# TEMPLATE_Circuit.net
KiCad netlist of a schematic drawn in Altium Designer
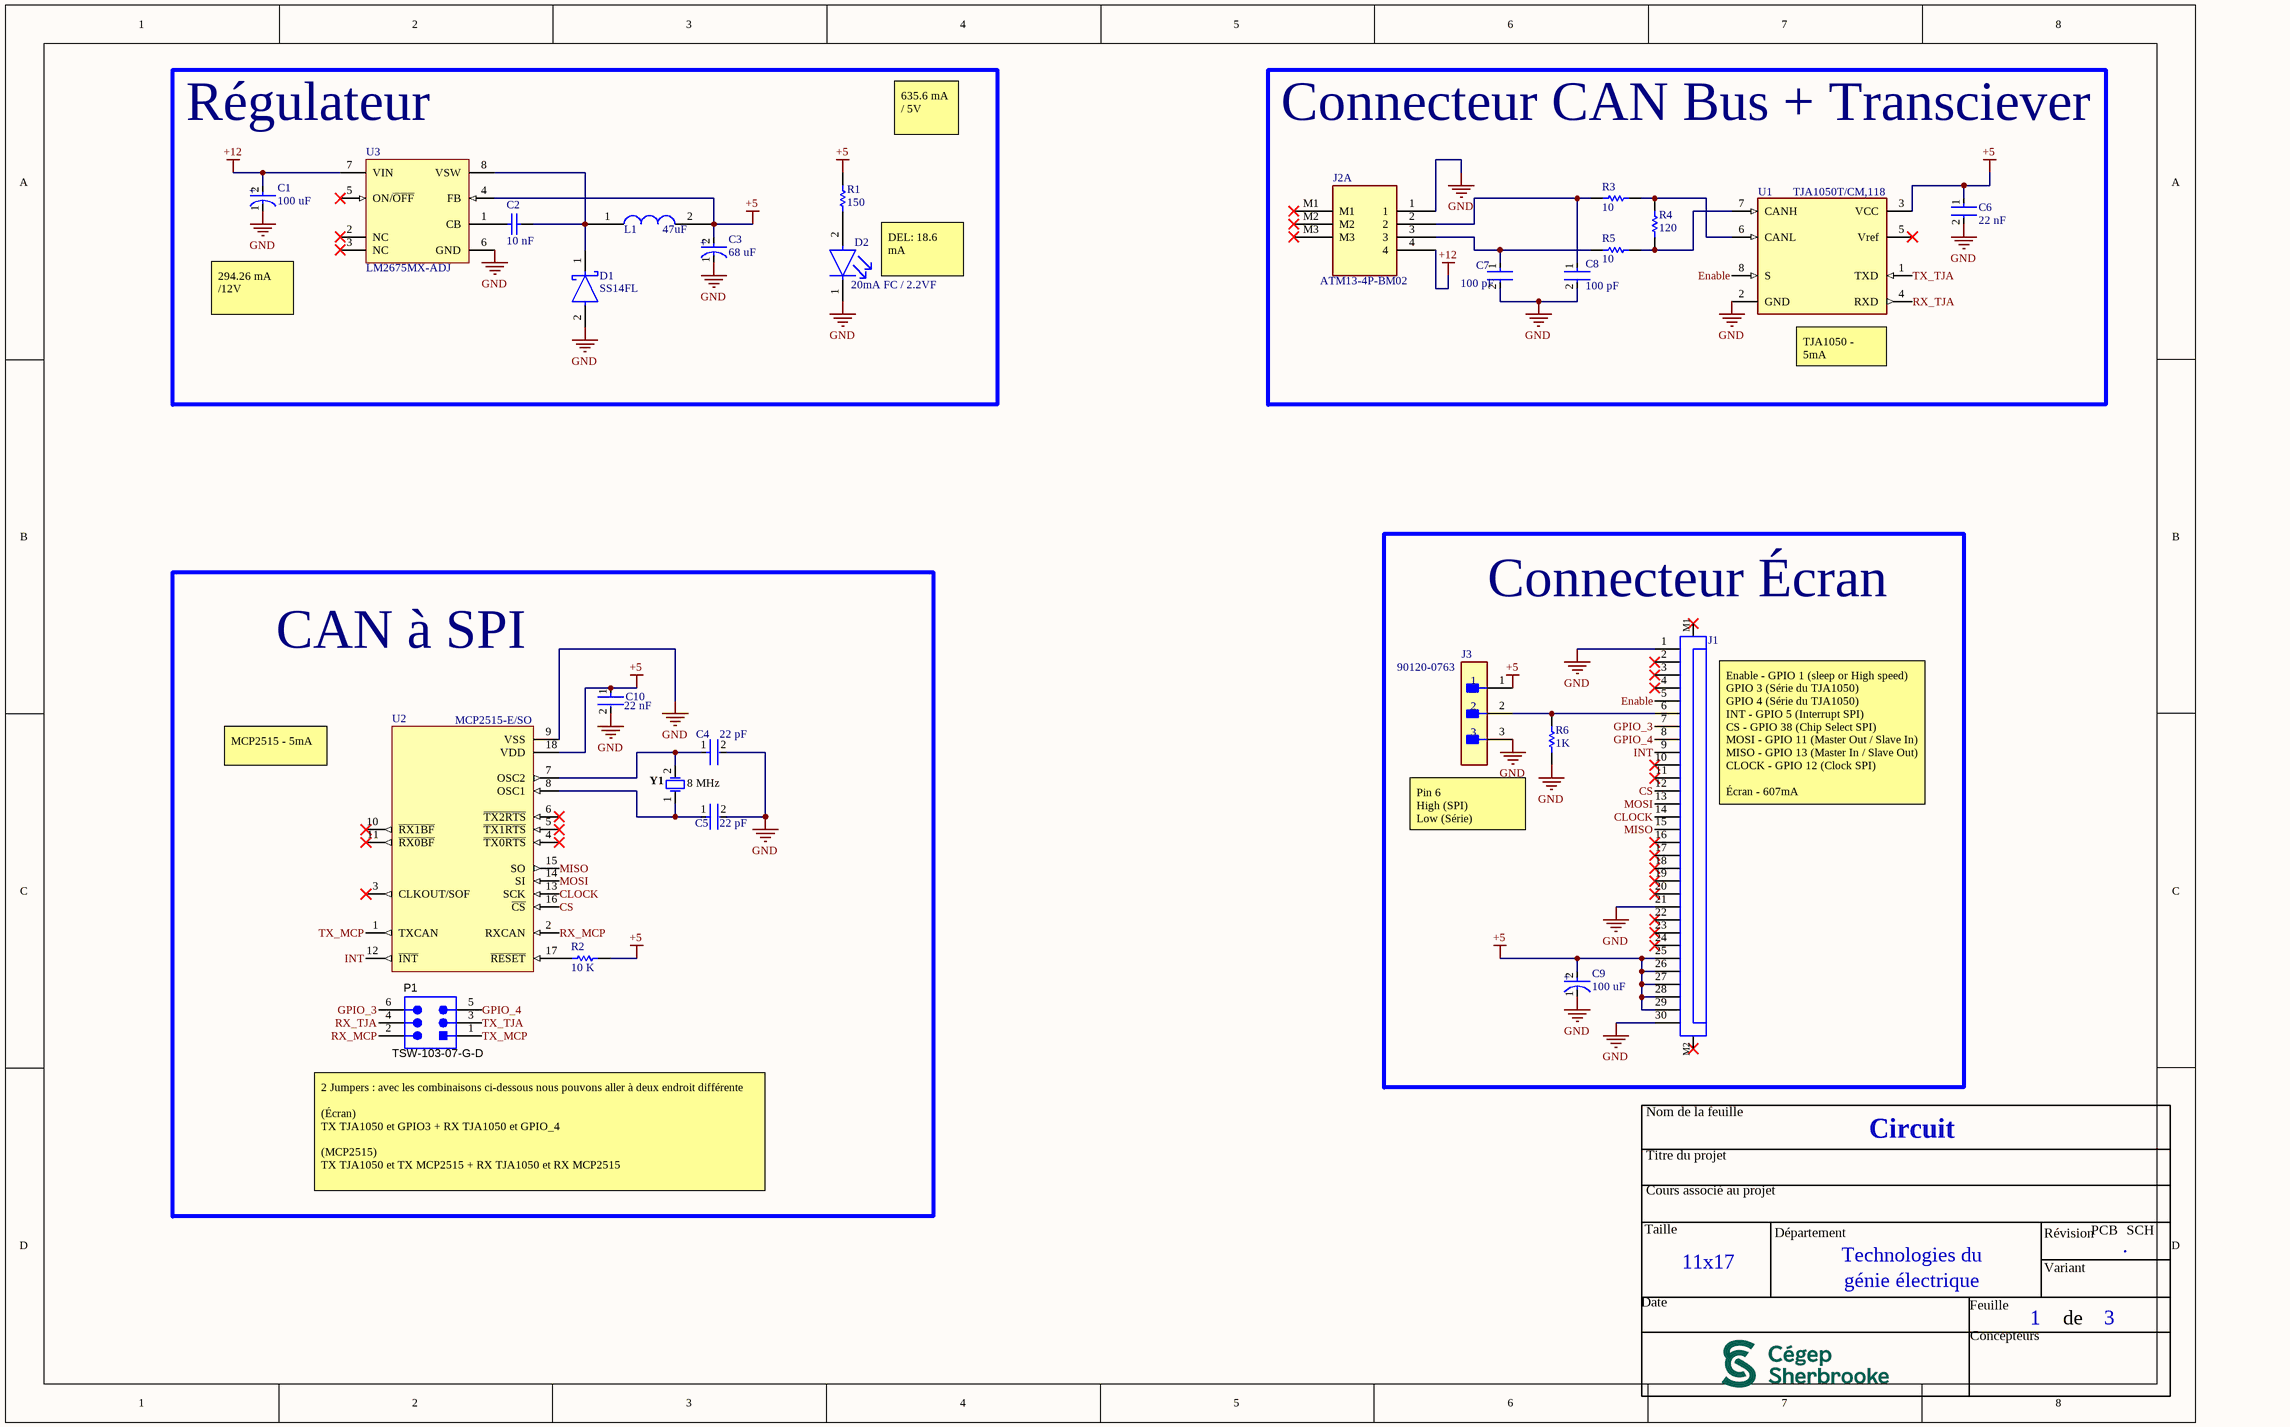
[diagram p0: TEMPLATE_Circuit.SchDoc]

(export (version "E")
  (design (tool "Eeschema 10.0.6"))
  (components
    (comp (ref "C1")
      (value "100 uF")
      (footprint "FP-FKF-MFG")
      (description "CAP ALUM 100UF 20% 50V SMD")
      (fields (field (name "VOLTAGE") "50V") (field (name "TOLERANCE") "20%"))
      (libsource (lib "Altium Content Vault") (part "a00bbbee19879c290e62620ae7e47b1"))
    )
    (comp (ref "C2")
      (value "10 nF")
      (footprint "CAPC1608X90X35ML10T15")
      (description "Chip Capacitor, 10 nF, +/- 10%, 50 V, -55 to 125 degC, 0603 (1608 Metric), RoHS, Tape and Reel")
      (fields (field (name "VOLTAGE") "50V") (field (name "TOLERANCE") "10%"))
      (libsource (lib "Altium Content Vault") (part "CAP-NP-2"))
    )
    (comp (ref "C3")
      (value "68 uF")
      (footprint "FP-OS-CON-SMT-F12-MFG")
      (description "Conductive Polymer Aluminum Solid Capacitors (OS-CON) 68uF ±20% 50V RADIAL SMT 10x12.6mm")
      (fields (field (name "TOLERANCE") "20%") (field (name "VOLTAGE") "50V"))
      (libsource (lib "Altium Content Vault") (part "a7907c86e72a156c28511143de7831b"))
    )
    (comp (ref "C4")
      (value "22 pF")
      (footprint "FP-C0805C-DN-MFG")
      (description "Capacitor; Ceramic; Cap; 22.0pF; Tol 5%; SMT; Vol-Rtg 50V; C0G; Tape and Reel")
      (fields
        (field (name "OCTOPART") "https://octopart.com/c0805c220j5gactu-kemet-145470")
        (field (name "MANUFACTURER") "KEMET")
      )
      (libsource (lib "Altium Content Vault") (part "b4654b650e69147ec39a6b967a45e02"))
    )
    (comp (ref "C5")
      (value "22 pF")
      (footprint "FP-C0805C-DN-MFG")
      (description "Capacitor; Ceramic; Cap; 22.0pF; Tol 5%; SMT; Vol-Rtg 50V; C0G; Tape and Reel")
      (fields
        (field (name "OCTOPART") "https://octopart.com/c0805c220j5gactu-kemet-145470")
        (field (name "MANUFACTURER") "KEMET")
      )
      (libsource (lib "Altium Content Vault") (part "b4654b650e69147ec39a6b967a45e02"))
    )
    (comp (ref "C6")
      (value "22 nF")
      (footprint "FP-C0805C-DN-MFG")
      (description "CAP CER 0.022UF 50V X7R 0805")
      (fields
        (field (name "MANUFACTURER") "KEMET")
        (field (name "MANUFACTURER PART NUMBER") "C0805C223K5RACTU")
      )
      (libsource (lib "Altium Content Vault") (part "b4654b650e69147ec39a6b967a45e02"))
    )
    (comp (ref "C7")
      (value "100 pF")
      (footprint "FP-CC0805-0_1-0_7-IPC_A")
      (description "CAP CER 100PF 50V C0G/NPO 0805")
      (fields (field (name "VOLTAGE") "50V") (field (name "TOLERANCE") "5%"))
      (libsource (lib "Altium Content Vault") (part "02cd4be3c70576c341d710602a673aa"))
    )
    (comp (ref "C8")
      (value "100 pF")
      (footprint "FP-CC0805-0_1-0_7-IPC_A")
      (description "CAP CER 100PF 50V C0G/NPO 0805")
      (fields (field (name "VOLTAGE") "50V") (field (name "TOLERANCE") "5%"))
      (libsource (lib "Altium Content Vault") (part "02cd4be3c70576c341d710602a673aa"))
    )
    (comp (ref "C9")
      (value "100 uF")
      (footprint "FP-FKF-MFG")
      (description "CAP ALUM 100UF 20% 50V SMD")
      (fields (field (name "VOLTAGE") "50V") (field (name "TOLERANCE") "20%"))
      (libsource (lib "Altium Content Vault") (part "a00bbbee19879c290e62620ae7e47b1"))
    )
    (comp (ref "C10")
      (value "22 nF")
      (footprint "FP-C0805C-DN-MFG")
      (description "CAP CER 0.022UF 50V X7R 0805")
      (fields
        (field (name "MANUFACTURER") "KEMET")
        (field (name "MANUFACTURER PART NUMBER") "C0805C223K5RACTU")
      )
      (libsource (lib "Altium Content Vault") (part "b4654b650e69147ec39a6b967a45e02"))
    )
    (comp (ref "D1")
      (value "SS14FL")
      (footprint "FP-425AD-MFG")
      (description "DIODE SCHOTTKY 40V 1A SOD123F")
      (fields
        (field (name "MANUFACTURER") "ON Semiconductor")
        (field (name "OCTOPART") "https://octopart.com/ss14fl-on+semiconductor-84331601")
      )
      (libsource (lib "Altium Content Vault") (part "c1678fac7984e62e0809fbf79c06691"))
    )
    (comp (ref "D2")
      (value "20mA FC / 2.2VF")
      (footprint "FP-SML-210-MFG")
      (description "LED GREEN CLEAR 0805 SMD")
      (fields (field (name "MANUFACTURER PART NUMBER") "SML-210MTT86") (field (name "MANUFACTURER") "ROHM"))
      (libsource (lib "Altium Content Vault") (part "8706943c75ba83719d021d2fdc84c58"))
    )
    (comp (ref "J1")
      (value "68613014422")
      (footprint "68613014422")
      (libsource (lib "Altium Content Vault") (part "FPC - 30P - 2MP"))
    )
    (comp (ref "J2")
      (value "ATM13-4P-BM02")
      (footprint "ATM134PBM02")
      (libsource (lib "PCB_MCP_Final") (part "ATM13-4P-BM02"))
    )
    (comp (ref "J3")
      (value "90120-0763")
      (footprint "FP-90120-0763-MFG")
      (description "CONN HEADER VERT 3POS 2.54MM")
      (fields
        (field (name "MANUFACTURER") "Molex")
        (field (name "OCTOPART") "https://octopart.com/90120-0763-molex-655433")
      )
      (libsource (lib "Altium Content Vault") (part "0d3f023dd272f625e17a2be33dea85f"))
    )
    (comp (ref "L1")
      (value "47uF")
      (footprint "NPI31W470MTRF")
      (libsource (lib "NPI31W470MTRF") (part "TEMPLATE_Circuit"))
    )
    (comp (ref "P1")
      (value "TSW-103-07-G-D")
      (footprint "SMTC-TSW-103-07-G-D_V")
      (fields (field (name "MANUFACTURER") "Samtec-Inc."))
      (libsource (lib "Altium Content Vault") (part "CN-2P-M-R6"))
    )
    (comp (ref "R1")
      (value "150")
      (footprint "RESC2013X60X40NL20T25")
      (fields (field (name "MANUFACTURER") "Panasonic") (field (name "PART NUMBER") "ERA6AEB151V"))
      (libsource (lib "Altium Content Vault") (part "RES"))
    )
    (comp (ref "R2")
      (value "10 K")
      (footprint "RESC2013X60X35NL10T20")
      (description "Chip Resistor, 10 KOhm, +/- 1%, 0.125 W, -55 to 155 degC, 0805 (2012 Metric), RoHS, Tape and Reel")
      (fields (field (name "MANUFACTURER") "Yageo"))
      (libsource (lib "Altium Content Vault") (part "RES-2"))
    )
    (comp (ref "R3")
      (value "10")
      (footprint "RESC2013X50X30NL20T20")
      (fields (field (name "MANUFACTURER") "Vishay Dale") (field (name "PART NUMBER") "CRCW080510R0FKEA"))
      (libsource (lib "Altium Content Vault") (part "RES"))
    )
    (comp (ref "R4")
      (value "120")
      (footprint "RESC2013X60X40ML20T25")
      (fields (field (name "MANUFACTURER") "Panasonic") (field (name "PART NUMBER") "ERA6AEB121V"))
      (libsource (lib "Altium Content Vault") (part "RES"))
    )
    (comp (ref "R5")
      (value "10")
      (footprint "RESC2013X50X30NL20T20")
      (fields (field (name "MANUFACTURER") "Vishay Dale") (field (name "PART NUMBER") "CRCW080510R0FKEA"))
      (libsource (lib "Altium Content Vault") (part "RES"))
    )
    (comp (ref "R6")
      (value "1K")
      (footprint "RESC2013X60X35ML10T20")
      (description "Chip Resistor, 1 KOhm, +/- 1%, 125 mW, -55 to 155 degC, 0805 (2012 Metric), RoHS, Tape and Reel")
      (fields (field (name "TOLERANCE") "1%") (field (name "MANUFACTURER") "Yageo"))
      (libsource (lib "Altium Content Vault") (part "RES-2"))
    )
    (comp (ref "U1")
      (value "TJA1050T/CM,118")
      (footprint "FP-SOT96-1-IPC_A")
      (description "IC TRANSCEIVER HALF 1/1 8SO")
      (libsource (lib "Altium Content Vault") (part "cfdefafd38a55dc0607790f57b8a78f"))
    )
    (comp (ref "U2")
      (value "MCP2515-E/SO")
      (footprint "SOIC-SO18_M")
      (description "Stand-Alone CAN Controller With SPI Interface, 18-Pin SOIC, Extended Temperature")
      (libsource (lib "Altium Content Vault") (part "COM-CAN-MCP2515-18"))
    )
    (comp (ref "U3")
      (value "LM2675MX-ADJ")
      (footprint "D0008A_N")
      (description "SIMPLE SWITCHER® Power Converter High Efficiency 1A Step-Down Voltage Regulator, 8-pin Narrow SOIC")
      (fields (field (name "MANUFACTURER") "Texas Instruments"))
      (libsource (lib "Altium Content Vault") (part "PM-REG-LM2675M-12"))
    )
    (comp (ref "Y1")
      (value "8 MHz")
      (footprint "FOX-HC49SDLF_V")
      (description "Resistance Weld Crystal, 8 MHz, +/- 30 ppm, -20 to 70 degC, 2-Pin SMD, RoHS, Tape and Reel")
      (fields (field (name "MANUFACTURER") "FOX Electronics") (field (name "TOLERANCE") "50ppm"))
      (libsource (lib "Altium Content Vault") (part "XTAL-1-2-2"))
    )
  )
  (nets
    (net (code "1") (name "+5") (class "Default")
      (node (ref "C10") (pin "1") (pinfunction "1_1") (pintype "passive"))
      (node (ref "C3") (pin "2") (pinfunction "A_2") (pintype "passive"))
      (node (ref "C6") (pin "1") (pinfunction "1_1") (pintype "passive"))
      (node (ref "C9") (pin "2") (pinfunction "A_2") (pintype "passive"))
      (node (ref "J1") (pin "25") (pinfunction "25_25") (pintype "passive"))
      (node (ref "J1") (pin "26") (pinfunction "26_26") (pintype "passive"))
      (node (ref "J1") (pin "27") (pinfunction "27_27") (pintype "passive"))
      (node (ref "J1") (pin "28") (pinfunction "28_28") (pintype "passive"))
      (node (ref "J1") (pin "29") (pinfunction "29_29") (pintype "passive"))
      (node (ref "J3") (pin "1") (pinfunction "1_1") (pintype "passive"))
      (node (ref "L1") (pin "2") (pinfunction "2_2") (pintype "passive"))
      (node (ref "R1") (pin "2") (pinfunction "2_2") (pintype "passive"))
      (node (ref "R2") (pin "2") (pinfunction "2_2") (pintype "passive"))
      (node (ref "U1") (pin "3") (pinfunction "VCC_3") (pintype "power_in"))
      (node (ref "U2") (pin "18") (pinfunction "VDD_18") (pintype "power_in"))
      (node (ref "U3") (pin "4") (pinfunction "FB_4") (pintype "input"))
    )
    (net (code "2") (name "+12") (class "Default")
      (node (ref "C1") (pin "2") (pinfunction "A_2") (pintype "passive"))
      (node (ref "J2") (pin "4") (pinfunction "4_4") (pintype "passive"))
      (node (ref "U3") (pin "7") (pinfunction "VIN_7") (pintype "power_in"))
    )
    (net (code "3") (name "/CLOCK") (class "Default")
      (node (ref "J1") (pin "14") (pinfunction "14_14") (pintype "passive"))
      (node (ref "U2") (pin "13") (pinfunction "SCK_13") (pintype "input"))
    )
    (net (code "4") (name "/CS") (class "Default")
      (node (ref "J1") (pin "12") (pinfunction "12_12") (pintype "passive"))
      (node (ref "U2") (pin "16") (pinfunction "~{CS}_16") (pintype "input"))
    )
    (net (code "5") (name "/Enable") (class "Default")
      (node (ref "J1") (pin "5") (pinfunction "5_5") (pintype "passive"))
      (node (ref "U1") (pin "8") (pinfunction "S_8") (pintype "input"))
    )
    (net (code "6") (name "/GPIO_3") (class "Default")
      (node (ref "J1") (pin "7") (pinfunction "7_7") (pintype "passive"))
      (node (ref "P1") (pin "6") (pinfunction "6_6") (pintype "passive"))
    )
    (net (code "7") (name "/GPIO_4") (class "Default")
      (node (ref "J1") (pin "8") (pinfunction "8_8") (pintype "passive"))
      (node (ref "P1") (pin "5") (pinfunction "5_5") (pintype "passive"))
    )
    (net (code "8") (name "/INT") (class "Default")
      (node (ref "J1") (pin "9") (pinfunction "9_9") (pintype "passive"))
      (node (ref "U2") (pin "12") (pinfunction "~{INT}_12") (pintype "output"))
    )
    (net (code "9") (name "/MISO") (class "Default")
      (node (ref "J1") (pin "15") (pinfunction "15_15") (pintype "passive"))
      (node (ref "U2") (pin "15") (pinfunction "SO_15") (pintype "output"))
    )
    (net (code "10") (name "/MOSI") (class "Default")
      (node (ref "J1") (pin "13") (pinfunction "13_13") (pintype "passive"))
      (node (ref "U2") (pin "14") (pinfunction "SI_14") (pintype "input"))
    )
    (net (code "11") (name "/RX_MCP") (class "Default")
      (node (ref "P1") (pin "2") (pinfunction "2_2") (pintype "passive"))
      (node (ref "U2") (pin "2") (pinfunction "RXCAN_2") (pintype "input"))
    )
    (net (code "12") (name "/RX_TJA") (class "Default")
      (node (ref "P1") (pin "4") (pinfunction "4_4") (pintype "passive"))
      (node (ref "U1") (pin "4") (pinfunction "RXD_4") (pintype "output"))
    )
    (net (code "13") (name "/TX_MCP") (class "Default")
      (node (ref "P1") (pin "1") (pinfunction "1_1") (pintype "passive"))
      (node (ref "U2") (pin "1") (pinfunction "TXCAN_1") (pintype "output"))
    )
    (net (code "14") (name "/TX_TJA") (class "Default")
      (node (ref "P1") (pin "3") (pinfunction "3_3") (pintype "passive"))
      (node (ref "U1") (pin "1") (pinfunction "TXD_1") (pintype "input"))
    )
    (net (code "15") (name "GND") (class "Default")
      (node (ref "C1") (pin "1") (pinfunction "C_1") (pintype "passive"))
      (node (ref "C10") (pin "2") (pinfunction "2_2") (pintype "passive"))
      (node (ref "C3") (pin "1") (pinfunction "C_1") (pintype "passive"))
      (node (ref "C4") (pin "2") (pinfunction "2_2") (pintype "passive"))
      (node (ref "C5") (pin "2") (pinfunction "2_2") (pintype "passive"))
      (node (ref "C6") (pin "2") (pinfunction "2_2") (pintype "passive"))
      (node (ref "C7") (pin "2") (pinfunction "2_2") (pintype "passive"))
      (node (ref "C8") (pin "2") (pinfunction "2_2") (pintype "passive"))
      (node (ref "C9") (pin "1") (pinfunction "C_1") (pintype "passive"))
      (node (ref "D1") (pin "2") (pinfunction "A_2") (pintype "passive"))
      (node (ref "D2") (pin "1") (pinfunction "C_1") (pintype "passive"))
      (node (ref "J1") (pin "1") (pinfunction "1_1") (pintype "passive"))
      (node (ref "J1") (pin "21") (pinfunction "21_21") (pintype "passive"))
      (node (ref "J1") (pin "30") (pinfunction "30_30") (pintype "passive"))
      (node (ref "J2") (pin "1") (pinfunction "1_1") (pintype "passive"))
      (node (ref "J3") (pin "3") (pinfunction "3_3") (pintype "passive"))
      (node (ref "R6") (pin "1") (pinfunction "1_1") (pintype "passive"))
      (node (ref "U1") (pin "2") (pinfunction "GND_2") (pintype "power_in"))
      (node (ref "U2") (pin "9") (pinfunction "VSS_9") (pintype "power_in"))
      (node (ref "U3") (pin "6") (pinfunction "GND_6") (pintype "power_in"))
    )
    (net (code "16") (name "Net-(C7-Pad1)") (class "Default")
      (node (ref "C7") (pin "1") (pinfunction "1_1") (pintype "passive"))
      (node (ref "J2") (pin "3") (pinfunction "3_3") (pintype "passive"))
      (node (ref "R5") (pin "1") (pinfunction "1_1") (pintype "passive"))
    )
    (net (code "17") (name "Net-(C8-Pad1)") (class "Default")
      (node (ref "C8") (pin "1") (pinfunction "1_1") (pintype "passive"))
      (node (ref "J2") (pin "2") (pinfunction "2_2") (pintype "passive"))
      (node (ref "R3") (pin "1") (pinfunction "1_1") (pintype "passive"))
    )
    (net (code "18") (name "Net-(D1-C)") (class "Default")
      (node (ref "C2") (pin "2") (pinfunction "2_2") (pintype "passive"))
      (node (ref "D1") (pin "1") (pinfunction "C_1") (pintype "passive"))
      (node (ref "L1") (pin "1") (pinfunction "1_1") (pintype "passive"))
      (node (ref "U3") (pin "8") (pinfunction "VSW_8") (pintype "power_in"))
    )
    (net (code "19") (name "Net-(D2-A)") (class "Default")
      (node (ref "D2") (pin "2") (pinfunction "A_2") (pintype "passive"))
      (node (ref "R1") (pin "1") (pinfunction "1_1") (pintype "passive"))
    )
    (net (code "20") (name "Net-(J1-Pad6)") (class "Default")
      (node (ref "J1") (pin "6") (pinfunction "6_6") (pintype "passive"))
      (node (ref "J3") (pin "2") (pinfunction "2_2") (pintype "passive"))
      (node (ref "R6") (pin "2") (pinfunction "2_2") (pintype "passive"))
    )
    (net (code "21") (name "Net-(U1-CANH)") (class "Default")
      (node (ref "R4") (pin "1") (pinfunction "1_1") (pintype "passive"))
      (node (ref "R5") (pin "2") (pinfunction "2_2") (pintype "passive"))
      (node (ref "U1") (pin "7") (pinfunction "CANH_7") (pintype "input"))
    )
    (net (code "22") (name "Net-(U1-CANL)") (class "Default")
      (node (ref "R3") (pin "2") (pinfunction "2_2") (pintype "passive"))
      (node (ref "R4") (pin "2") (pinfunction "2_2") (pintype "passive"))
      (node (ref "U1") (pin "6") (pinfunction "CANL_6") (pintype "input"))
    )
    (net (code "23") (name "Net-(U2-OSC1)") (class "Default")
      (node (ref "C5") (pin "1") (pinfunction "1_1") (pintype "passive"))
      (node (ref "U2") (pin "8") (pinfunction "OSC1_8") (pintype "input"))
      (node (ref "Y1") (pin "1") (pinfunction "1_1") (pintype "passive"))
    )
    (net (code "24") (name "Net-(U2-OSC2)") (class "Default")
      (node (ref "C4") (pin "1") (pinfunction "1_1") (pintype "passive"))
      (node (ref "U2") (pin "7") (pinfunction "OSC2_7") (pintype "output"))
      (node (ref "Y1") (pin "2") (pinfunction "2_2") (pintype "passive"))
    )
    (net (code "25") (name "Net-(U2-~{RESET})") (class "Default")
      (node (ref "R2") (pin "1") (pinfunction "1_1") (pintype "passive"))
      (node (ref "U2") (pin "17") (pinfunction "~{RESET}_17") (pintype "input"))
    )
    (net (code "26") (name "Net-(U3-CB)") (class "Default")
      (node (ref "C2") (pin "1") (pinfunction "1_1") (pintype "passive"))
      (node (ref "U3") (pin "1") (pinfunction "CB_1") (pintype "passive"))
    )
    (net (code "27") (name "unconnected-(J1-Pad2)") (class "Default")
      (node (ref "J1") (pin "2") (pinfunction "2_2") (pintype "passive+no_connect"))
    )
    (net (code "28") (name "unconnected-(J1-Pad3)") (class "Default")
      (node (ref "J1") (pin "3") (pinfunction "3_3") (pintype "passive+no_connect"))
    )
    (net (code "29") (name "unconnected-(J1-Pad4)") (class "Default")
      (node (ref "J1") (pin "4") (pinfunction "4_4") (pintype "passive+no_connect"))
    )
    (net (code "30") (name "unconnected-(J1-Pad10)") (class "Default")
      (node (ref "J1") (pin "10") (pinfunction "10_10") (pintype "passive+no_connect"))
    )
    (net (code "31") (name "unconnected-(J1-Pad11)") (class "Default")
      (node (ref "J1") (pin "11") (pinfunction "11_11") (pintype "passive+no_connect"))
    )
    (net (code "32") (name "unconnected-(J1-Pad16)") (class "Default")
      (node (ref "J1") (pin "16") (pinfunction "16_16") (pintype "passive+no_connect"))
    )
    (net (code "33") (name "unconnected-(J1-Pad17)") (class "Default")
      (node (ref "J1") (pin "17") (pinfunction "17_17") (pintype "passive+no_connect"))
    )
    (net (code "34") (name "unconnected-(J1-Pad18)") (class "Default")
      (node (ref "J1") (pin "18") (pinfunction "18_18") (pintype "passive+no_connect"))
    )
    (net (code "35") (name "unconnected-(J1-Pad19)") (class "Default")
      (node (ref "J1") (pin "19") (pinfunction "19_19") (pintype "passive+no_connect"))
    )
    (net (code "36") (name "unconnected-(J1-Pad20)") (class "Default")
      (node (ref "J1") (pin "20") (pinfunction "20_20") (pintype "passive+no_connect"))
    )
    (net (code "37") (name "unconnected-(J1-Pad22)") (class "Default")
      (node (ref "J1") (pin "22") (pinfunction "22_22") (pintype "passive+no_connect"))
    )
    (net (code "38") (name "unconnected-(J1-Pad23)") (class "Default")
      (node (ref "J1") (pin "23") (pinfunction "23_23") (pintype "passive+no_connect"))
    )
    (net (code "39") (name "unconnected-(J1-Pad24)") (class "Default")
      (node (ref "J1") (pin "24") (pinfunction "24_24") (pintype "passive+no_connect"))
    )
    (net (code "40") (name "unconnected-(J1-PadM1)") (class "Default")
      (node (ref "J1") (pin "M1") (pinfunction "M1_M1") (pintype "passive+no_connect"))
    )
    (net (code "41") (name "unconnected-(J1-PadM2)") (class "Default")
      (node (ref "J1") (pin "M2") (pinfunction "M2_M2") (pintype "passive+no_connect"))
    )
    (net (code "42") (name "unconnected-(J2-PadM1)") (class "Default")
      (node (ref "J2") (pin "M1") (pinfunction "M1_M1") (pintype "passive+no_connect"))
    )
    (net (code "43") (name "unconnected-(J2-PadM2)") (class "Default")
      (node (ref "J2") (pin "M2") (pinfunction "M2_M2") (pintype "passive+no_connect"))
    )
    (net (code "44") (name "unconnected-(J2-PadM3)") (class "Default")
      (node (ref "J2") (pin "M3") (pinfunction "M3_M3") (pintype "passive+no_connect"))
    )
    (net (code "45") (name "unconnected-(U1-Vref-Pad5)") (class "Default")
      (node (ref "U1") (pin "5") (pinfunction "Vref_5") (pintype "power_in+no_connect"))
    )
    (net (code "46") (name "unconnected-(U2-CLKOUT{slash}SOF-Pad3)") (class "Default")
      (node (ref "U2") (pin "3") (pinfunction "CLKOUT/SOF_3") (pintype "output+no_connect"))
    )
    (net (code "47") (name "unconnected-(U2-~{RX0BF}-Pad11)") (class "Default")
      (node (ref "U2") (pin "11") (pinfunction "~{RX0BF}_11") (pintype "output+no_connect"))
    )
    (net (code "48") (name "unconnected-(U2-~{RX1BF}-Pad10)") (class "Default")
      (node (ref "U2") (pin "10") (pinfunction "~{RX1BF}_10") (pintype "output+no_connect"))
    )
    (net (code "49") (name "unconnected-(U2-~{TX0RTS}-Pad4)") (class "Default")
      (node (ref "U2") (pin "4") (pinfunction "~{TX0RTS}_4") (pintype "input+no_connect"))
    )
    (net (code "50") (name "unconnected-(U2-~{TX1RTS}-Pad5)") (class "Default")
      (node (ref "U2") (pin "5") (pinfunction "~{TX1RTS}_5") (pintype "input+no_connect"))
    )
    (net (code "51") (name "unconnected-(U2-~{TX2RTS}-Pad6)") (class "Default")
      (node (ref "U2") (pin "6") (pinfunction "~{TX2RTS}_6") (pintype "input+no_connect"))
    )
    (net (code "52") (name "unconnected-(U3-NC-Pad2)") (class "Default")
      (node (ref "U3") (pin "2") (pinfunction "NC_2") (pintype "passive+no_connect"))
    )
    (net (code "53") (name "unconnected-(U3-NC-Pad3)") (class "Default")
      (node (ref "U3") (pin "3") (pinfunction "NC_3") (pintype "passive+no_connect"))
    )
    (net (code "54") (name "unconnected-(U3-ON{slash}~{OFF}-Pad5)") (class "Default")
      (node (ref "U3") (pin "5") (pinfunction "ON/~{OFF}_5") (pintype "input+no_connect"))
    )
  )
)
